# 3DR-GPS-LEA6-JST-v11-RELEASE.net
KiCad netlist of a schematic drawn in EAGLE
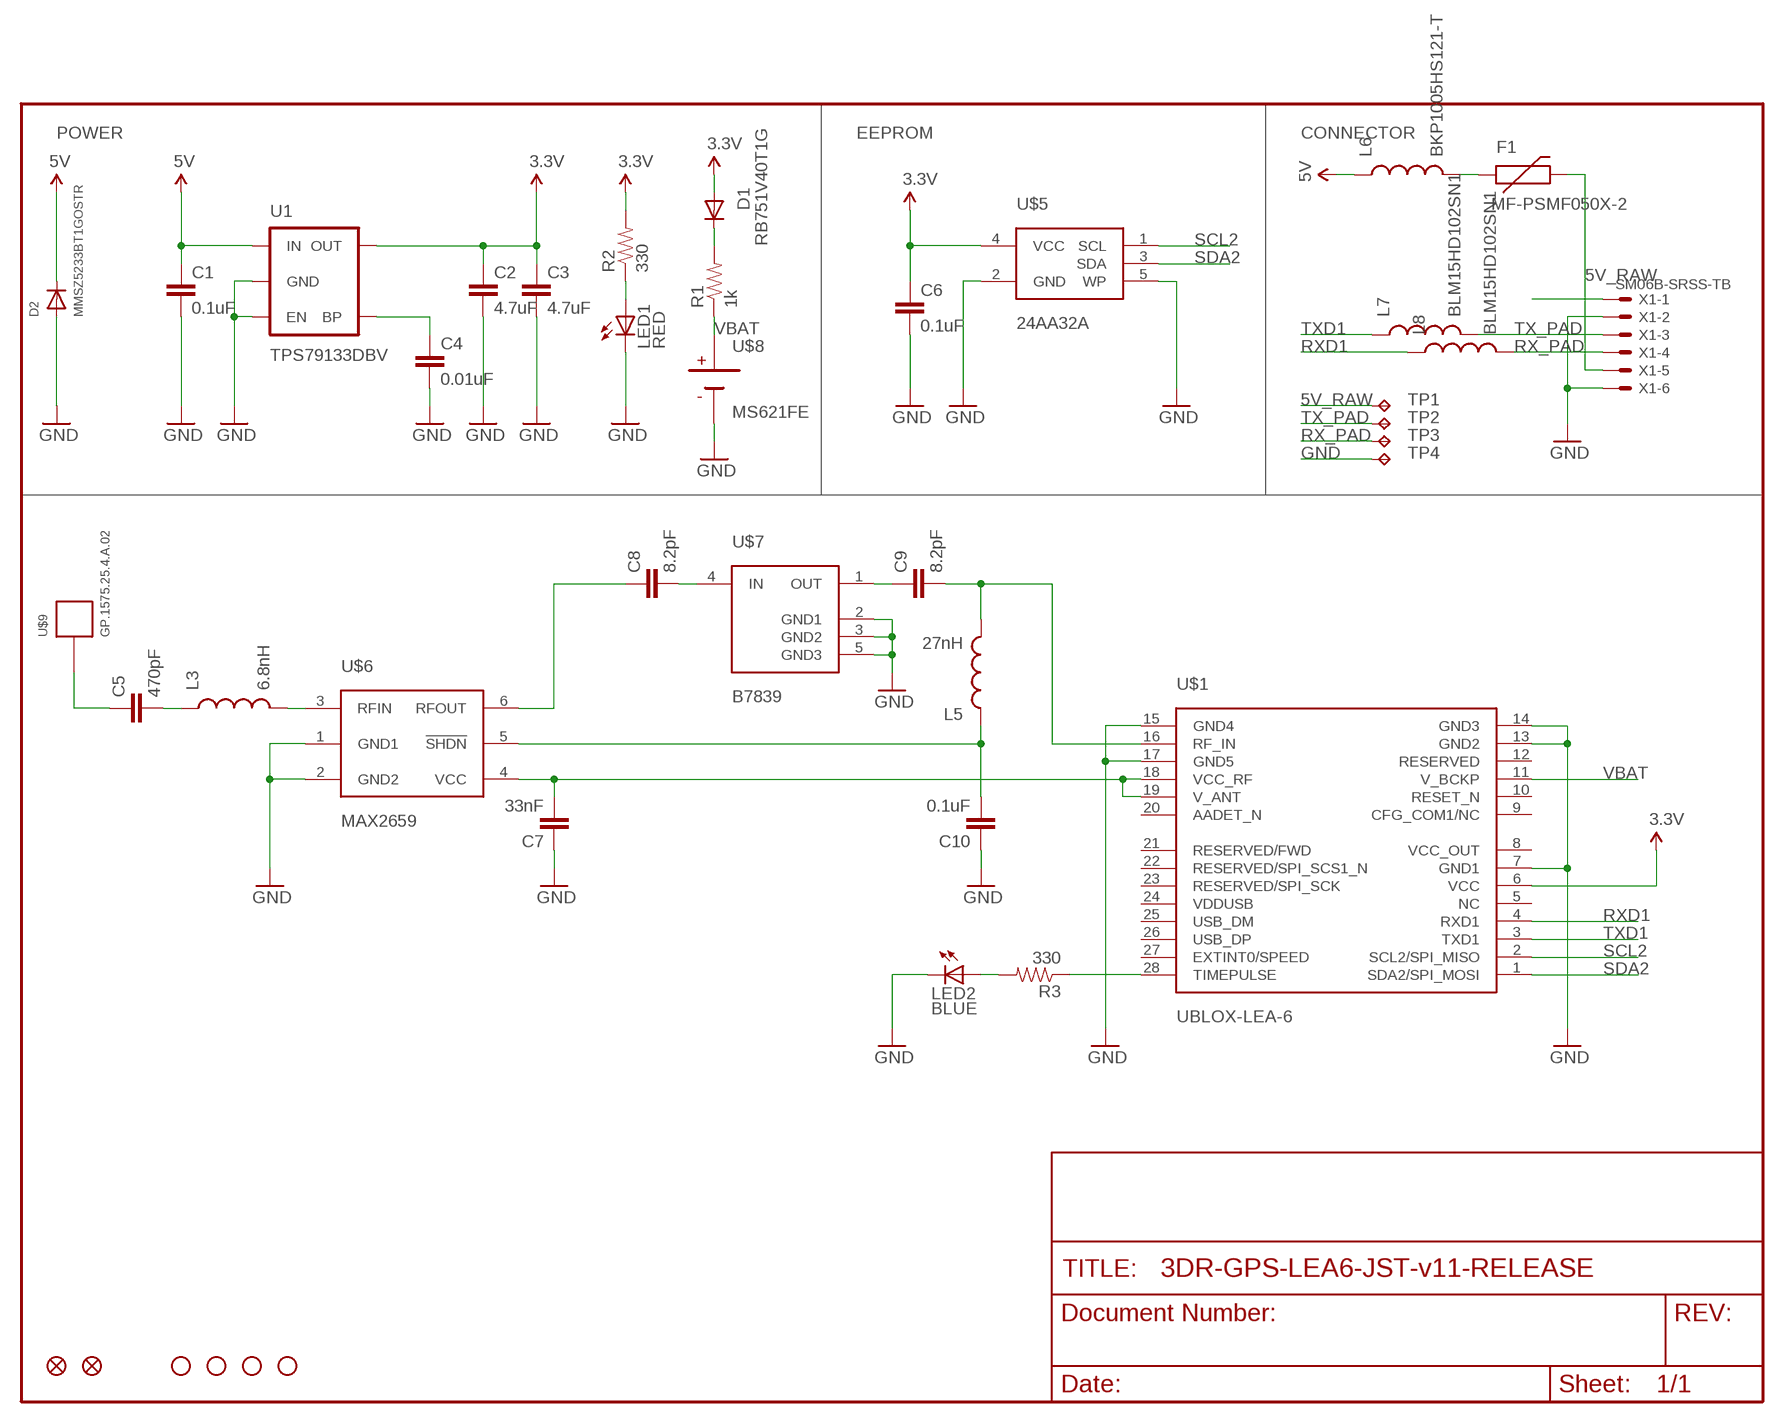
[diagram p0: schematic, sheet 1]

(export (version "E")
  (design (tool "Eeschema 10.0.6"))
  (components
    (comp (ref "C1")
      (value "0.1uF")
      (footprint "eagle-import:0402-CAP")
      (libsource (lib "eagle-import") (part "CAP0402-CAP"))
    )
    (comp (ref "C2")
      (value "4.7uF")
      (footprint "eagle-import:0805")
      (libsource (lib "eagle-import") (part "CAP0805"))
    )
    (comp (ref "C3")
      (value "4.7uF")
      (footprint "eagle-import:0805")
      (libsource (lib "eagle-import") (part "CAP0805"))
    )
    (comp (ref "C4")
      (value "0.01uF")
      (footprint "eagle-import:0402-CAP")
      (libsource (lib "eagle-import") (part "CAP0402-CAP"))
    )
    (comp (ref "C5")
      (value "470pF")
      (footprint "eagle-import:0402-CAP")
      (libsource (lib "eagle-import") (part "CAP0402-CAP"))
    )
    (comp (ref "C6")
      (value "0.1uF")
      (footprint "eagle-import:0402-CAP")
      (libsource (lib "eagle-import") (part "CAP0402-CAP"))
    )
    (comp (ref "C7")
      (value "33nF")
      (footprint "eagle-import:0402-CAP")
      (libsource (lib "eagle-import") (part "CAP0402-CAP"))
    )
    (comp (ref "C8")
      (value "8.2pF")
      (footprint "eagle-import:0402-CAP")
      (libsource (lib "eagle-import") (part "CAP0402-CAP"))
    )
    (comp (ref "C9")
      (value "8.2pF")
      (footprint "eagle-import:0402-CAP")
      (libsource (lib "eagle-import") (part "CAP0402-CAP"))
    )
    (comp (ref "C10")
      (value "0.1uF")
      (footprint "eagle-import:0402-CAP")
      (libsource (lib "eagle-import") (part "CAP0402-CAP"))
    )
    (comp (ref "D1")
      (value "RB751V40T1G")
      (footprint "eagle-import:SOD-323")
      (libsource (lib "eagle-import") (part "DIODESOD"))
    )
    (comp (ref "D2")
      (value "MMSZ5233BT1GOSTR")
      (footprint "eagle-import:SOD-123")
      (libsource (lib "eagle-import") (part "DIODESOD-123"))
    )
    (comp (ref "F1")
      (value "MF-PSMF050X-2")
      (footprint "eagle-import:0805")
      (libsource (lib "eagle-import") (part "PTC"))
    )
    (comp (ref "JP1")
      (value "FIDUCIAL1X2")
      (footprint "eagle-import:FIDUCIAL-1X2")
      (libsource (lib "eagle-import") (part "FIDUCIAL1X2"))
    )
    (comp (ref "JP2")
      (value "FIDUCIAL1X2")
      (footprint "eagle-import:FIDUCIAL-1X2")
      (libsource (lib "eagle-import") (part "FIDUCIAL1X2"))
    )
    (comp (ref "JP3")
      (value "STAND-OFF")
      (footprint "eagle-import:STAND-OFF")
      (libsource (lib "eagle-import") (part "STAND-OFF"))
    )
    (comp (ref "JP4")
      (value "STAND-OFF")
      (footprint "eagle-import:STAND-OFF")
      (libsource (lib "eagle-import") (part "STAND-OFF"))
    )
    (comp (ref "JP5")
      (value "STAND-OFF")
      (footprint "eagle-import:STAND-OFF")
      (libsource (lib "eagle-import") (part "STAND-OFF"))
    )
    (comp (ref "JP6")
      (value "STAND-OFF")
      (footprint "eagle-import:STAND-OFF")
      (libsource (lib "eagle-import") (part "STAND-OFF"))
    )
    (comp (ref "L3")
      (value "6.8nH")
      (footprint "eagle-import:C0402")
      (libsource (lib "eagle-import") (part "INDUCTOR0402"))
    )
    (comp (ref "L5")
      (value "27nH")
      (footprint "eagle-import:C0402")
      (libsource (lib "eagle-import") (part "INDUCTOR0402"))
    )
    (comp (ref "L6")
      (value "BKP1005HS121-T")
      (footprint "eagle-import:0402-IND")
      (libsource (lib "eagle-import") (part "pixhawk2_INDUCTOR0402"))
    )
    (comp (ref "L7")
      (value "BLM15HD102SN1")
      (footprint "eagle-import:0402-IND")
      (libsource (lib "eagle-import") (part "pixhawk2_INDUCTOR0402"))
    )
    (comp (ref "L8")
      (value "BLM15HD102SN1")
      (footprint "eagle-import:0402-IND")
      (libsource (lib "eagle-import") (part "pixhawk2_INDUCTOR0402"))
    )
    (comp (ref "LED1")
      (value "RED")
      (footprint "eagle-import:LED-0603")
      (libsource (lib "eagle-import") (part "LED0603"))
    )
    (comp (ref "LED2")
      (value "BLUE")
      (footprint "eagle-import:LED-0603")
      (libsource (lib "eagle-import") (part "LED0603"))
    )
    (comp (ref "R1")
      (value "1k")
      (footprint "eagle-import:0402-RES")
      (libsource (lib "eagle-import") (part "RESISTOR0402-RES"))
    )
    (comp (ref "R2")
      (value "330")
      (footprint "eagle-import:0402-RES")
      (libsource (lib "eagle-import") (part "RESISTOR0402-RES"))
    )
    (comp (ref "R3")
      (value "330")
      (footprint "eagle-import:0402-RES")
      (libsource (lib "eagle-import") (part "RESISTOR0402-RES"))
    )
    (comp (ref "TP1")
      (value "TPTP20SQ")
      (footprint "eagle-import:TP20SQ")
      (libsource (lib "eagle-import") (part "TPTP20SQ"))
    )
    (comp (ref "TP2")
      (value "TPTP20SQ")
      (footprint "eagle-import:TP20SQ")
      (libsource (lib "eagle-import") (part "TPTP20SQ"))
    )
    (comp (ref "TP3")
      (value "TPTP20SQ")
      (footprint "eagle-import:TP20SQ")
      (libsource (lib "eagle-import") (part "TPTP20SQ"))
    )
    (comp (ref "TP4")
      (value "TPTP20SQ")
      (footprint "eagle-import:TP20SQ")
      (libsource (lib "eagle-import") (part "TPTP20SQ"))
    )
    (comp (ref "U$1")
      (value "UBLOX-LEA-6")
      (footprint "eagle-import:UBLOX-LEA-6")
      (libsource (lib "eagle-import") (part "UBLOX-LEA-6"))
    )
    (comp (ref "U$5")
      (value "24AA32A")
      (footprint "eagle-import:SOT23-5")
      (libsource (lib "eagle-import") (part "24AA32A"))
    )
    (comp (ref "U$6")
      (value "MAX2659")
      (footprint "eagle-import:UDFN-6")
      (libsource (lib "eagle-import") (part "MAX2659"))
    )
    (comp (ref "U$7")
      (value "B7839")
      (footprint "eagle-import:QCS5E")
      (libsource (lib "eagle-import") (part "B7839"))
    )
    (comp (ref "U$8")
      (value "MS621FE")
      (footprint "eagle-import:MS621FE")
      (libsource (lib "eagle-import") (part "MS621FE"))
    )
    (comp (ref "U$9")
      (value "GP.1575.25.4.A.02")
      (footprint "eagle-import:GP.1575.25.4.A.02")
      (libsource (lib "eagle-import") (part "GP.1575.25.4.A.02"))
    )
    (comp (ref "U1")
      (value "TPS79133DBV")
      (footprint "eagle-import:SOT23-5")
      (libsource (lib "eagle-import") (part "V_REG_LDOSMD"))
    )
    (comp (ref "X1")
      (value "SM06B-SRSS-TB")
      (footprint "eagle-import:SM06B-SRSS-TB")
      (libsource (lib "eagle-import") (part "?M06B-SRSS-TBS"))
    )
  )
  (nets
    (net (code "1") (name "/5V_RAW") (class "Default")
      (node (ref "F1") (pin "2") (pinfunction "2_2") (pintype "bidirectional"))
      (node (ref "TP1") (pin "TP") (pinfunction "TP_TP") (pintype "input"))
      (node (ref "X1") (pin "5") (pinfunction "S_5") (pintype "passive"))
    )
    (net (code "2") (name "/RXD1") (class "Default")
      (node (ref "L8") (pin "1") (pinfunction "1_1") (pintype "passive"))
      (node (ref "U$1") (pin "4") (pinfunction "RXD1_4") (pintype "bidirectional"))
    )
    (net (code "3") (name "/RX_PAD") (class "Default")
      (node (ref "L8") (pin "2") (pinfunction "2_2") (pintype "passive"))
      (node (ref "TP3") (pin "TP") (pinfunction "TP_TP") (pintype "input"))
      (node (ref "X1") (pin "4") (pinfunction "S_4") (pintype "passive"))
    )
    (net (code "4") (name "/SCL2") (class "Default")
      (node (ref "U$1") (pin "2") (pinfunction "SCL2/SPI_MISO_2") (pintype "bidirectional"))
      (node (ref "U$5") (pin "1") (pinfunction "SCL_1") (pintype "bidirectional"))
    )
    (net (code "5") (name "/SDA2") (class "Default")
      (node (ref "U$1") (pin "1") (pinfunction "SDA2/SPI_MOSI_1") (pintype "bidirectional"))
      (node (ref "U$5") (pin "3") (pinfunction "SDA_3") (pintype "bidirectional"))
    )
    (net (code "6") (name "/TXD1") (class "Default")
      (node (ref "L7") (pin "1") (pinfunction "1_1") (pintype "passive"))
      (node (ref "U$1") (pin "3") (pinfunction "TXD1_3") (pintype "bidirectional"))
    )
    (net (code "7") (name "/TX_PAD") (class "Default")
      (node (ref "L7") (pin "2") (pinfunction "2_2") (pintype "passive"))
      (node (ref "TP2") (pin "TP") (pinfunction "TP_TP") (pintype "input"))
      (node (ref "X1") (pin "3") (pinfunction "S_3") (pintype "passive"))
    )
    (net (code "8") (name "/VBAT") (class "Default")
      (node (ref "R1") (pin "1") (pinfunction "1_1") (pintype "passive"))
      (node (ref "U$1") (pin "11") (pinfunction "V_BCKP_11") (pintype "bidirectional"))
      (node (ref "U$8") (pin "1") (pinfunction "POS_1") (pintype "bidirectional"))
    )
    (net (code "9") (name "3.3V") (class "Default")
      (node (ref "C2") (pin "1") (pinfunction "1_1") (pintype "passive"))
      (node (ref "C3") (pin "1") (pinfunction "1_1") (pintype "passive"))
      (node (ref "C6") (pin "1") (pinfunction "1_1") (pintype "passive"))
      (node (ref "D1") (pin "2") (pinfunction "A_2") (pintype "passive"))
      (node (ref "R2") (pin "2") (pinfunction "2_2") (pintype "passive"))
      (node (ref "U$1") (pin "6") (pinfunction "VCC_6") (pintype "bidirectional"))
      (node (ref "U$5") (pin "4") (pinfunction "VCC_4") (pintype "bidirectional"))
      (node (ref "U1") (pin "5") (pinfunction "OUT_5") (pintype "passive"))
    )
    (net (code "10") (name "5V") (class "Default")
      (node (ref "C1") (pin "1") (pinfunction "1_1") (pintype "passive"))
      (node (ref "D2") (pin "C") (pinfunction "C_C") (pintype "passive"))
      (node (ref "L6") (pin "1") (pinfunction "1_1") (pintype "passive"))
      (node (ref "U1") (pin "1") (pinfunction "IN_1") (pintype "input"))
    )
    (net (code "11") (name "GND") (class "Default")
      (node (ref "C1") (pin "2") (pinfunction "2_2") (pintype "passive"))
      (node (ref "C10") (pin "1") (pinfunction "1_1") (pintype "passive"))
      (node (ref "C2") (pin "2") (pinfunction "2_2") (pintype "passive"))
      (node (ref "C3") (pin "2") (pinfunction "2_2") (pintype "passive"))
      (node (ref "C4") (pin "2") (pinfunction "2_2") (pintype "passive"))
      (node (ref "C6") (pin "2") (pinfunction "2_2") (pintype "passive"))
      (node (ref "C7") (pin "1") (pinfunction "1_1") (pintype "passive"))
      (node (ref "D2") (pin "A") (pinfunction "A_A") (pintype "passive"))
      (node (ref "LED1") (pin "C") (pinfunction "C_C") (pintype "passive"))
      (node (ref "LED2") (pin "C") (pinfunction "C_C") (pintype "passive"))
      (node (ref "TP4") (pin "TP") (pinfunction "TP_TP") (pintype "input"))
      (node (ref "U$1") (pin "13") (pinfunction "GND2_13") (pintype "bidirectional"))
      (node (ref "U$1") (pin "14") (pinfunction "GND3_14") (pintype "bidirectional"))
      (node (ref "U$1") (pin "15") (pinfunction "GND4_15") (pintype "bidirectional"))
      (node (ref "U$1") (pin "17") (pinfunction "GND5_17") (pintype "bidirectional"))
      (node (ref "U$1") (pin "7") (pinfunction "GND1_7") (pintype "bidirectional"))
      (node (ref "U$5") (pin "2") (pinfunction "GND_2") (pintype "bidirectional"))
      (node (ref "U$5") (pin "5") (pinfunction "WP_5") (pintype "bidirectional"))
      (node (ref "U$6") (pin "1") (pinfunction "GND1_1") (pintype "bidirectional"))
      (node (ref "U$6") (pin "2") (pinfunction "GND2_2") (pintype "bidirectional"))
      (node (ref "U$7") (pin "2") (pinfunction "GND1_2") (pintype "bidirectional"))
      (node (ref "U$7") (pin "3") (pinfunction "GND2_3") (pintype "bidirectional"))
      (node (ref "U$7") (pin "5") (pinfunction "GND3_5") (pintype "bidirectional"))
      (node (ref "U$8") (pin "2") (pinfunction "NEG_2") (pintype "bidirectional"))
      (node (ref "U1") (pin "2") (pinfunction "GND_2") (pintype "input"))
      (node (ref "U1") (pin "3") (pinfunction "EN_3") (pintype "input"))
      (node (ref "X1") (pin "2") (pinfunction "S_2") (pintype "passive"))
      (node (ref "X1") (pin "6") (pinfunction "S_6") (pintype "passive"))
    )
    (net (code "12") (name "Net-(C5-Pad2)") (class "Default")
      (node (ref "C5") (pin "2") (pinfunction "2_2") (pintype "passive"))
      (node (ref "L3") (pin "1") (pinfunction "1_1") (pintype "passive"))
    )
    (net (code "13") (name "Net-(D1-C)") (class "Default")
      (node (ref "D1") (pin "1") (pinfunction "C_1") (pintype "passive"))
      (node (ref "R1") (pin "2") (pinfunction "2_2") (pintype "passive"))
    )
    (net (code "14") (name "Net-(F1-Pad1)") (class "Default")
      (node (ref "F1") (pin "1") (pinfunction "1_1") (pintype "bidirectional"))
      (node (ref "L6") (pin "2") (pinfunction "2_2") (pintype "passive"))
    )
    (net (code "15") (name "Net-(LED1-PadA)") (class "Default")
      (node (ref "LED1") (pin "A") (pinfunction "A_A") (pintype "passive"))
      (node (ref "R2") (pin "1") (pinfunction "1_1") (pintype "passive"))
    )
    (net (code "16") (name "Net-(LED2-PadA)") (class "Default")
      (node (ref "LED2") (pin "A") (pinfunction "A_A") (pintype "passive"))
      (node (ref "R3") (pin "2") (pinfunction "2_2") (pintype "passive"))
    )
    (net (code "17") (name "Net-(U$1-RF_IN)") (class "Default")
      (node (ref "C9") (pin "2") (pinfunction "2_2") (pintype "passive"))
      (node (ref "L5") (pin "2") (pinfunction "2_2") (pintype "passive"))
      (node (ref "U$1") (pin "16") (pinfunction "RF_IN_16") (pintype "bidirectional"))
    )
    (net (code "18") (name "Net-(U$1-TIMEPULSE)") (class "Default")
      (node (ref "R3") (pin "1") (pinfunction "1_1") (pintype "passive"))
      (node (ref "U$1") (pin "28") (pinfunction "TIMEPULSE_28") (pintype "bidirectional"))
    )
    (net (code "19") (name "Net-(U$1-VCC_RF)") (class "Default")
      (node (ref "C7") (pin "2") (pinfunction "2_2") (pintype "passive"))
      (node (ref "U$1") (pin "18") (pinfunction "VCC_RF_18") (pintype "bidirectional"))
      (node (ref "U$1") (pin "19") (pinfunction "V_ANT_19") (pintype "bidirectional"))
      (node (ref "U$6") (pin "4") (pinfunction "VCC_4") (pintype "bidirectional"))
    )
    (net (code "20") (name "Net-(U$6-RFIN)") (class "Default")
      (node (ref "L3") (pin "2") (pinfunction "2_2") (pintype "passive"))
      (node (ref "U$6") (pin "3") (pinfunction "RFIN_3") (pintype "bidirectional"))
    )
    (net (code "21") (name "Net-(U$6-RFOUT)") (class "Default")
      (node (ref "C8") (pin "1") (pinfunction "1_1") (pintype "passive"))
      (node (ref "U$6") (pin "6") (pinfunction "RFOUT_6") (pintype "bidirectional"))
    )
    (net (code "22") (name "Net-(U$6-~{SHDN})") (class "Default")
      (node (ref "C10") (pin "2") (pinfunction "2_2") (pintype "passive"))
      (node (ref "L5") (pin "1") (pinfunction "1_1") (pintype "passive"))
      (node (ref "U$6") (pin "5") (pinfunction "~{SHDN}_5") (pintype "bidirectional"))
    )
    (net (code "23") (name "Net-(U$7-IN)") (class "Default")
      (node (ref "C8") (pin "2") (pinfunction "2_2") (pintype "passive"))
      (node (ref "U$7") (pin "4") (pinfunction "IN_4") (pintype "bidirectional"))
    )
    (net (code "24") (name "Net-(U$7-OUT)") (class "Default")
      (node (ref "C9") (pin "1") (pinfunction "1_1") (pintype "passive"))
      (node (ref "U$7") (pin "1") (pinfunction "OUT_1") (pintype "bidirectional"))
    )
    (net (code "25") (name "Net-(U$9-PIN)") (class "Default")
      (node (ref "C5") (pin "1") (pinfunction "1_1") (pintype "passive"))
      (node (ref "U$9") (pin "1") (pinfunction "PIN_1") (pintype "bidirectional"))
    )
    (net (code "26") (name "Net-(U1-BP)") (class "Default")
      (node (ref "C4") (pin "1") (pinfunction "1_1") (pintype "passive"))
      (node (ref "U1") (pin "4") (pinfunction "BP_4") (pintype "input"))
    )
    (net (code "27") (name "unconnected-(U$1-AADET_N-Pad20)") (class "Default")
      (node (ref "U$1") (pin "20") (pinfunction "AADET_N_20") (pintype "bidirectional"))
    )
    (net (code "28") (name "unconnected-(U$1-CFG_COM1{slash}NC-Pad9)") (class "Default")
      (node (ref "U$1") (pin "9") (pinfunction "CFG_COM1/NC_9") (pintype "bidirectional"))
    )
    (net (code "29") (name "unconnected-(U$1-EXTINT0{slash}SPEED-Pad27)") (class "Default")
      (node (ref "U$1") (pin "27") (pinfunction "EXTINT0/SPEED_27") (pintype "bidirectional"))
    )
    (net (code "30") (name "unconnected-(U$1-NC-Pad5)") (class "Default")
      (node (ref "U$1") (pin "5") (pinfunction "NC_5") (pintype "bidirectional"))
    )
    (net (code "31") (name "unconnected-(U$1-RESERVED-Pad12)") (class "Default")
      (node (ref "U$1") (pin "12") (pinfunction "RESERVED_12") (pintype "bidirectional"))
    )
    (net (code "32") (name "unconnected-(U$1-RESERVED{slash}FWD-Pad21)") (class "Default")
      (node (ref "U$1") (pin "21") (pinfunction "RESERVED/FWD_21") (pintype "bidirectional"))
    )
    (net (code "33") (name "unconnected-(U$1-RESERVED{slash}SPI_SCK-Pad23)") (class "Default")
      (node (ref "U$1") (pin "23") (pinfunction "RESERVED/SPI_SCK_23") (pintype "bidirectional"))
    )
    (net (code "34") (name "unconnected-(U$1-RESERVED{slash}SPI_SCS1_N-Pad22)") (class "Default")
      (node (ref "U$1") (pin "22") (pinfunction "RESERVED/SPI_SCS1_N_22") (pintype "bidirectional"))
    )
    (net (code "35") (name "unconnected-(U$1-RESET_N-Pad10)") (class "Default")
      (node (ref "U$1") (pin "10") (pinfunction "RESET_N_10") (pintype "bidirectional"))
    )
    (net (code "36") (name "unconnected-(U$1-USB_DM-Pad25)") (class "Default")
      (node (ref "U$1") (pin "25") (pinfunction "USB_DM_25") (pintype "bidirectional"))
    )
    (net (code "37") (name "unconnected-(U$1-USB_DP-Pad26)") (class "Default")
      (node (ref "U$1") (pin "26") (pinfunction "USB_DP_26") (pintype "bidirectional"))
    )
    (net (code "38") (name "unconnected-(U$1-VCC_OUT-Pad8)") (class "Default")
      (node (ref "U$1") (pin "8") (pinfunction "VCC_OUT_8") (pintype "bidirectional"))
    )
    (net (code "39") (name "unconnected-(U$1-VDDUSB-Pad24)") (class "Default")
      (node (ref "U$1") (pin "24") (pinfunction "VDDUSB_24") (pintype "bidirectional"))
    )
    (net (code "40") (name "unconnected-(X1A-S-Pad1)") (class "Default")
      (node (ref "X1") (pin "1") (pinfunction "S_1") (pintype "passive"))
    )
  )
)
